# rapidshark_motor_lulz.net
KiCad netlist of a schematic drawn in EAGLE
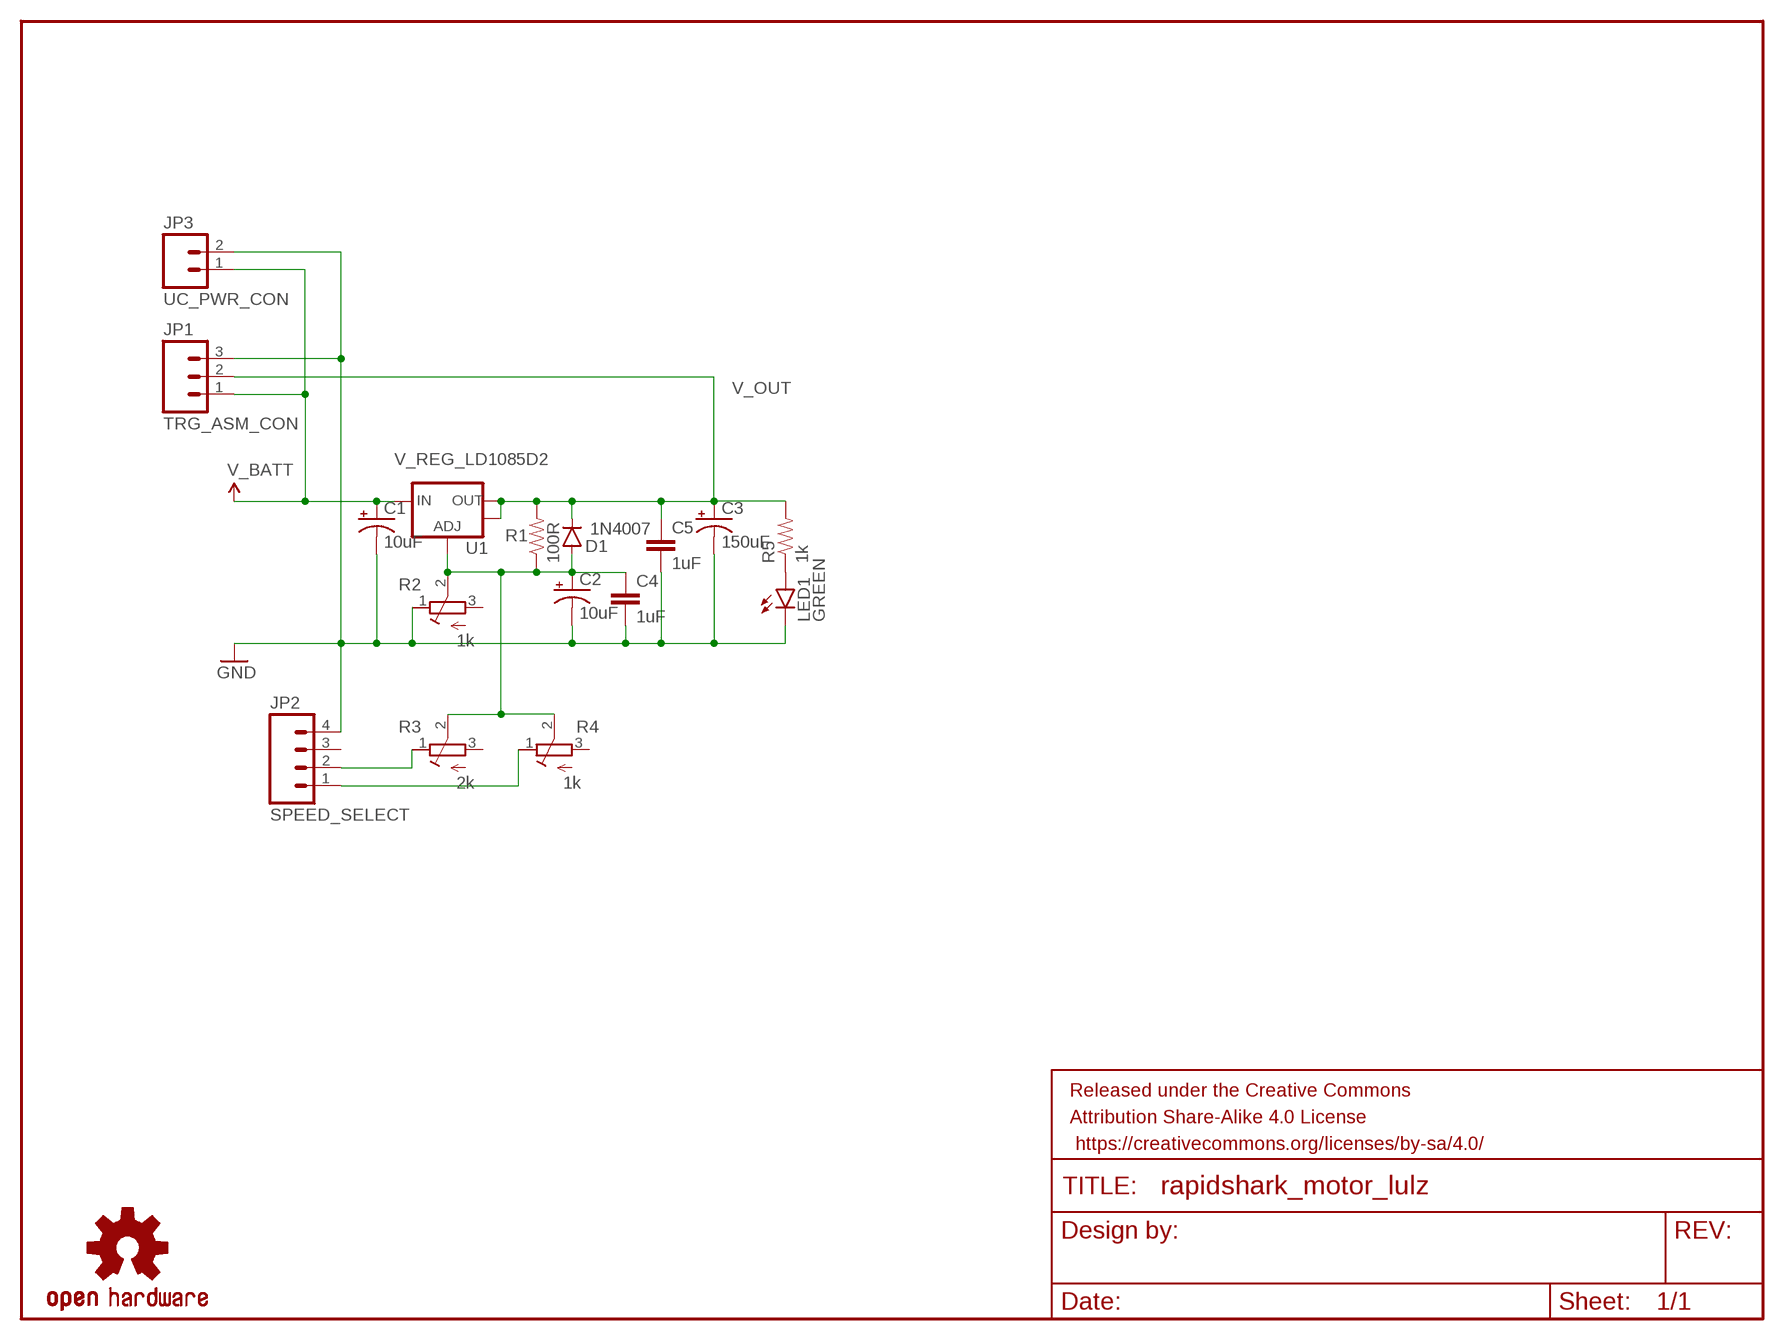
[diagram p0: schematic, sheet 1]

(export (version "E")
  (design (tool "Eeschema 10.0.6"))
  (components
    (comp (ref "C1")
      (value "10uF")
      (footprint "eagle-import:E2-5")
      (libsource (lib "eagle-import") (part "CPOL-USE2-5"))
    )
    (comp (ref "C2")
      (value "10uF")
      (footprint "eagle-import:E2-5")
      (libsource (lib "eagle-import") (part "CPOL-USE2-5"))
    )
    (comp (ref "C3")
      (value "150uF")
      (footprint "eagle-import:TT5D11L")
      (libsource (lib "eagle-import") (part "CPOL-USTT5D11L"))
    )
    (comp (ref "C4")
      (value "1uF")
      (footprint "eagle-import:CAP-PTH-SMALL")
      (libsource (lib "eagle-import") (part "CAPPTH"))
    )
    (comp (ref "C5")
      (value "1uF")
      (footprint "eagle-import:CAP-PTH-SMALL")
      (libsource (lib "eagle-import") (part "CAPPTH"))
    )
    (comp (ref "D1")
      (value "1N4007")
      (footprint "eagle-import:DIODE-1N4001")
      (libsource (lib "eagle-import") (part "DIODEPTH"))
    )
    (comp (ref "FRAME1")
      (value "FRAME-LETTER")
      (footprint "eagle-import:CREATIVE_COMMONS")
      (libsource (lib "eagle-import") (part "FRAME-LETTER"))
    )
    (comp (ref "JP1")
      (value "TRG_ASM_CON")
      (footprint "eagle-import:SCREWTERMINAL-5MM-3")
      (libsource (lib "eagle-import") (part "M03-SCREW-5MM"))
    )
    (comp (ref "JP2")
      (value "SPEED_SELECT")
      (footprint "eagle-import:1X04")
      (libsource (lib "eagle-import") (part "M04PTH"))
    )
    (comp (ref "JP3")
      (value "UC_PWR_CON")
      (footprint "eagle-import:1X02")
      (libsource (lib "eagle-import") (part "M02PTH"))
    )
    (comp (ref "LED1")
      (value "GREEN")
      (footprint "eagle-import:LED3MM")
      (libsource (lib "eagle-import") (part "LED3MM"))
    )
    (comp (ref "LOGO1")
      (value "OSHW-LOGOS")
      (footprint "eagle-import:OSHW-LOGO-S")
      (libsource (lib "eagle-import") (part "OSHW-LOGOS"))
    )
    (comp (ref "R1")
      (value "100R")
      (footprint "eagle-import:AXIAL-0.3")
      (libsource (lib "eagle-import") (part "RESISTORAXIAL-0.3"))
    )
    (comp (ref "R2")
      (value "1k")
      (footprint "eagle-import:RTRIMT93XA")
      (libsource (lib "eagle-import") (part "R-TRIMMT93XA"))
    )
    (comp (ref "R3")
      (value "2k")
      (footprint "eagle-import:RTRIMT93XA")
      (libsource (lib "eagle-import") (part "R-TRIMMT93XA"))
    )
    (comp (ref "R4")
      (value "1k")
      (footprint "eagle-import:RTRIMT93XA")
      (libsource (lib "eagle-import") (part "R-TRIMMT93XA"))
    )
    (comp (ref "R5")
      (value "1k")
      (footprint "eagle-import:AXIAL-0.3")
      (libsource (lib "eagle-import") (part "RESISTORAXIAL-0.3"))
    )
    (comp (ref "U1")
      (value "V_REG_LD1085D2")
      (footprint "eagle-import:D2PACK_A")
      (libsource (lib "eagle-import") (part "V_REG_LD1085D2"))
    )
  )
  (nets
    (net (code "1") (name "/V_OUT") (class "Default")
      (node (ref "C3") (pin "+") (pinfunction "+_+") (pintype "passive"))
      (node (ref "C5") (pin "1") (pinfunction "1_1") (pintype "passive"))
      (node (ref "D1") (pin "C") (pinfunction "C_C") (pintype "passive"))
      (node (ref "JP1") (pin "2") (pinfunction "2_2") (pintype "passive"))
      (node (ref "R1") (pin "P$2") (pinfunction "2_P$2") (pintype "passive"))
      (node (ref "R5") (pin "P$2") (pinfunction "2_P$2") (pintype "passive"))
      (node (ref "U1") (pin "2") (pinfunction "OUT_2") (pintype "output"))
      (node (ref "U1") (pin "TAB") (pinfunction "OUT_TAB") (pintype "output"))
    )
    (net (code "2") (name "GND") (class "Default")
      (node (ref "C1") (pin "-") (pinfunction "-_-") (pintype "passive"))
      (node (ref "C2") (pin "-") (pinfunction "-_-") (pintype "passive"))
      (node (ref "C3") (pin "-") (pinfunction "-_-") (pintype "passive"))
      (node (ref "C4") (pin "2") (pinfunction "2_2") (pintype "passive"))
      (node (ref "C5") (pin "2") (pinfunction "2_2") (pintype "passive"))
      (node (ref "JP1") (pin "3") (pinfunction "3_3") (pintype "passive"))
      (node (ref "JP2") (pin "4") (pinfunction "4_4") (pintype "passive"))
      (node (ref "JP3") (pin "2") (pinfunction "2_2") (pintype "passive"))
      (node (ref "LED1") (pin "K") (pinfunction "C_K") (pintype "passive"))
      (node (ref "R2") (pin "1") (pinfunction "A_1") (pintype "passive"))
    )
    (net (code "3") (name "Net-(R1-1)") (class "Default")
      (node (ref "C2") (pin "+") (pinfunction "+_+") (pintype "passive"))
      (node (ref "C4") (pin "1") (pinfunction "1_1") (pintype "passive"))
      (node (ref "D1") (pin "A") (pinfunction "A_A") (pintype "passive"))
      (node (ref "R1") (pin "P$1") (pinfunction "1_P$1") (pintype "passive"))
      (node (ref "R2") (pin "2") (pinfunction "S_2") (pintype "passive"))
      (node (ref "R3") (pin "2") (pinfunction "S_2") (pintype "passive"))
      (node (ref "R4") (pin "2") (pinfunction "S_2") (pintype "passive"))
      (node (ref "U1") (pin "1") (pinfunction "ADJ_1") (pintype "input"))
    )
    (net (code "4") (name "Net-(R3-A)") (class "Default")
      (node (ref "JP2") (pin "2") (pinfunction "2_2") (pintype "passive"))
      (node (ref "R3") (pin "1") (pinfunction "A_1") (pintype "passive"))
    )
    (net (code "5") (name "Net-(R4-A)") (class "Default")
      (node (ref "JP2") (pin "1") (pinfunction "1_1") (pintype "passive"))
      (node (ref "R4") (pin "1") (pinfunction "A_1") (pintype "passive"))
    )
    (net (code "6") (name "Net-(R5-1)") (class "Default")
      (node (ref "LED1") (pin "A") (pinfunction "A_A") (pintype "passive"))
      (node (ref "R5") (pin "P$1") (pinfunction "1_P$1") (pintype "passive"))
    )
    (net (code "7") (name "V_BATT") (class "Default")
      (node (ref "C1") (pin "+") (pinfunction "+_+") (pintype "passive"))
      (node (ref "JP1") (pin "1") (pinfunction "1_1") (pintype "passive"))
      (node (ref "JP3") (pin "1") (pinfunction "1_1") (pintype "passive"))
      (node (ref "U1") (pin "3") (pinfunction "IN_3") (pintype "input"))
    )
    (net (code "8") (name "unconnected-(JP2-Pad3)") (class "Default")
      (node (ref "JP2") (pin "3") (pinfunction "3_3") (pintype "passive"))
    )
    (net (code "9") (name "unconnected-(R2-E-Pad3)") (class "Default")
      (node (ref "R2") (pin "3") (pinfunction "E_3") (pintype "passive"))
    )
    (net (code "10") (name "unconnected-(R3-E-Pad3)") (class "Default")
      (node (ref "R3") (pin "3") (pinfunction "E_3") (pintype "passive"))
    )
    (net (code "11") (name "unconnected-(R4-E-Pad3)") (class "Default")
      (node (ref "R4") (pin "3") (pinfunction "E_3") (pintype "passive"))
    )
  )
)
